# Ampli_audio.net
KiCad netlist of a schematic drawn in EasyEDA
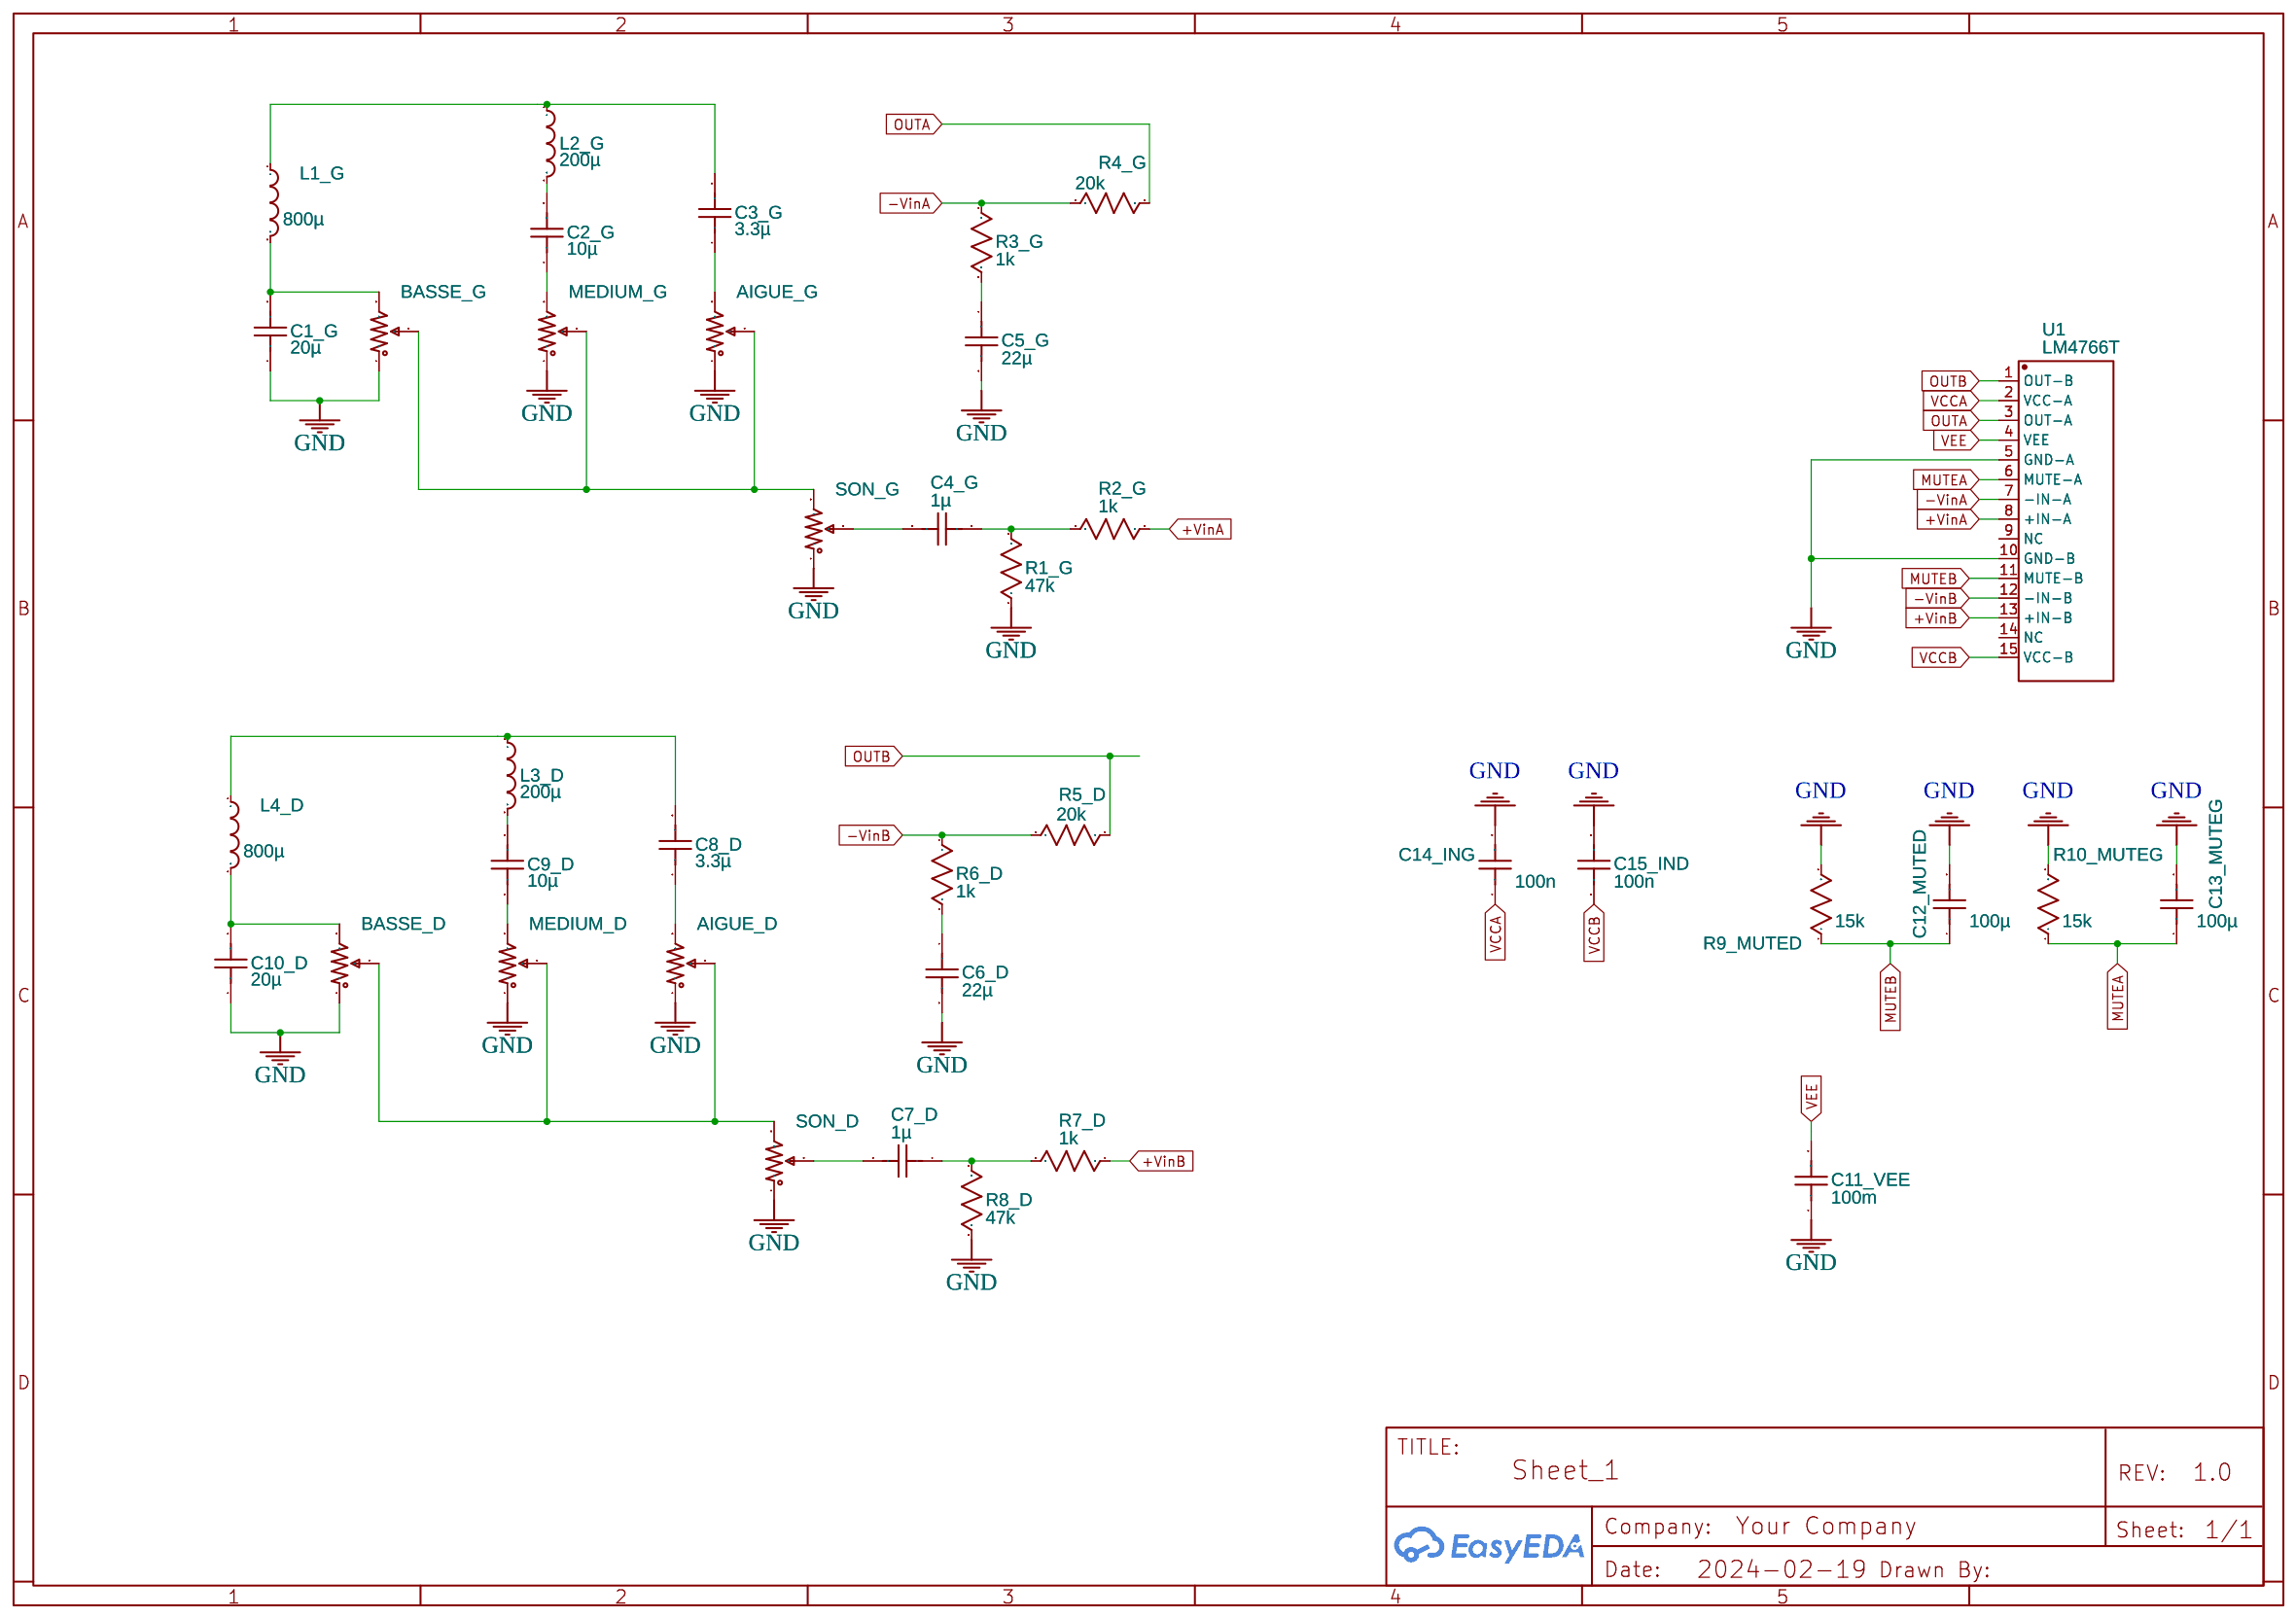
[diagram p0: schematic sheet]

(export (version "E")
  (design (tool "Eeschema 10.0.6"))
  (components
    (comp (ref "AIGUE_D") (value "R_3386P_US") (libsource (lib "") (part "R_3386P_US_3")))
    (comp (ref "AIGUE_G") (value "R_3386P_US") (libsource (lib "") (part "R_3386P_US_4")))
    (comp (ref "BASSE_D") (value "R_3386P_US") (libsource (lib "") (part "R_3386P_US_6")))
    (comp (ref "BASSE_G") (value "R_3386P_US") (libsource (lib "") (part "R_3386P_US_7")))
    (comp (ref "C1_G") (value "20µ") (libsource (lib "") (part "C_0603_US_11")))
    (comp (ref "C2_G") (value "10µ") (libsource (lib "") (part "C_0603_US_14")))
    (comp (ref "C3_G") (value "3.3µ") (libsource (lib "") (part "C_0603_US_12")))
    (comp (ref "C4_G") (value "1µ") (libsource (lib "") (part "C_0603_US_3")))
    (comp (ref "C5_G") (value "22µ") (libsource (lib "") (part "C_0603_US_10")))
    (comp (ref "C6_D") (value "22µ") (libsource (lib "") (part "C_0603_US_13")))
    (comp (ref "C7_D") (value "1µ") (libsource (lib "") (part "C_0603_US_6")))
    (comp (ref "C8_D") (value "3.3µ") (libsource (lib "") (part "C_0603_US_8")))
    (comp (ref "C9_D") (value "10µ") (libsource (lib "") (part "C_0603_US")))
    (comp (ref "C10_D") (value "20µ") (libsource (lib "") (part "C_0603_US_5")))
    (comp (ref "C11_VEE") (value "100m") (libsource (lib "") (part "C_0603_US_7")))
    (comp (ref "C12_MUTED") (value "100µ") (libsource (lib "") (part "C_0603_US_9")))
    (comp (ref "C13_MUTEG") (value "100µ") (libsource (lib "") (part "C_0603_US_4")))
    (comp (ref "C14_ING") (value "100n") (libsource (lib "") (part "C_0603_US_1")))
    (comp (ref "C15_IND") (value "100n") (libsource (lib "") (part "C_0603_US_2")))
    (comp (ref "L1_G") (value "800µ") (libsource (lib "") (part "L0603_US_3")))
    (comp (ref "L2_G") (value "200µ") (libsource (lib "") (part "L0603_US_1")))
    (comp (ref "L3_D") (value "200µ") (libsource (lib "") (part "L0603_US")))
    (comp (ref "L4_D") (value "800µ") (libsource (lib "") (part "L0603_US_2")))
    (comp (ref "MEDIUM_D") (value "R_3386P_US") (libsource (lib "") (part "R_3386P_US")))
    (comp (ref "MEDIUM_G") (value "R_3386P_US") (libsource (lib "") (part "R_3386P_US_1")))
    (comp (ref "R1_G") (value "47k") (libsource (lib "") (part "R_0603_US_5")))
    (comp (ref "R2_G") (value "1k") (libsource (lib "") (part "R_0603_US_3")))
    (comp (ref "R3_G") (value "1k") (libsource (lib "") (part "R_0603_US")))
    (comp (ref "R4_G") (value "20k") (libsource (lib "") (part "R_0603_US_6")))
    (comp (ref "R5_D") (value "20k") (libsource (lib "") (part "R_0603_US_1")))
    (comp (ref "R6_D") (value "1k") (libsource (lib "") (part "R_0603_US_7")))
    (comp (ref "R7_D") (value "1k") (libsource (lib "") (part "R_0603_US_4")))
    (comp (ref "R8_D") (value "47k") (libsource (lib "") (part "R_0603_US_2")))
    (comp (ref "R9_MUTED") (value "15k") (libsource (lib "") (part "R_0603_US_8")))
    (comp (ref "R10_MUTEG") (value "15k") (libsource (lib "") (part "R_0603_US_9")))
    (comp (ref "SON_D") (value "R_3386P_US") (libsource (lib "") (part "R_3386P_US_5")))
    (comp (ref "SON_G") (value "R_3386P_US") (libsource (lib "") (part "R_3386P_US_2")))
    (comp (ref "U1")
      (value "LM4766T")
      (fields (field (name "Manufacturer Part") "LM4766T/NOPB") (field (name "Manufacturer") "TI(德州仪器)"))
      (libsource (lib "") (part "LM4766T"))
    )
  )
  (nets
    (net (code "1") (name "+VinA") (class "Default")
      (node (ref "R2_G") (pin "1") (pinfunction "1_1") (pintype "unspecified"))
      (node (ref "U1") (pin "8") (pinfunction "+IN-A_8") (pintype "unspecified"))
    )
    (net (code "2") (name "+VinB") (class "Default")
      (node (ref "R7_D") (pin "1") (pinfunction "1_1") (pintype "unspecified"))
      (node (ref "U1") (pin "13") (pinfunction "+IN-B_13") (pintype "unspecified"))
    )
    (net (code "3") (name "-VinA") (class "Default")
      (node (ref "R3_G") (pin "1") (pinfunction "1_1") (pintype "unspecified"))
      (node (ref "R4_G") (pin "1") (pinfunction "1_1") (pintype "unspecified"))
      (node (ref "U1") (pin "7") (pinfunction "-IN-A_7") (pintype "unspecified"))
    )
    (net (code "4") (name "-VinB") (class "Default")
      (node (ref "R5_D") (pin "1") (pinfunction "1_1") (pintype "unspecified"))
      (node (ref "R6_D") (pin "1") (pinfunction "1_1") (pintype "unspecified"))
      (node (ref "U1") (pin "12") (pinfunction "-IN-B_12") (pintype "unspecified"))
    )
    (net (code "5") (name "GND") (class "Default")
      (node (ref "AIGUE_D") (pin "1") (pinfunction "1_1") (pintype "unspecified"))
      (node (ref "AIGUE_G") (pin "1") (pinfunction "1_1") (pintype "unspecified"))
      (node (ref "BASSE_D") (pin "1") (pinfunction "1_1") (pintype "unspecified"))
      (node (ref "BASSE_G") (pin "1") (pinfunction "1_1") (pintype "unspecified"))
      (node (ref "C10_D") (pin "1") (pinfunction "1_1") (pintype "unspecified"))
      (node (ref "C11_VEE") (pin "1") (pinfunction "1_1") (pintype "unspecified"))
      (node (ref "C12_MUTED") (pin "2") (pinfunction "2_2") (pintype "unspecified"))
      (node (ref "C13_MUTEG") (pin "2") (pinfunction "2_2") (pintype "unspecified"))
      (node (ref "C14_ING") (pin "2") (pinfunction "2_2") (pintype "unspecified"))
      (node (ref "C15_IND") (pin "2") (pinfunction "2_2") (pintype "unspecified"))
      (node (ref "C1_G") (pin "1") (pinfunction "1_1") (pintype "unspecified"))
      (node (ref "C5_G") (pin "2") (pinfunction "2_2") (pintype "unspecified"))
      (node (ref "C6_D") (pin "2") (pinfunction "2_2") (pintype "unspecified"))
      (node (ref "MEDIUM_D") (pin "1") (pinfunction "1_1") (pintype "unspecified"))
      (node (ref "MEDIUM_G") (pin "1") (pinfunction "1_1") (pintype "unspecified"))
      (node (ref "R10_MUTEG") (pin "2") (pinfunction "2_2") (pintype "unspecified"))
      (node (ref "R1_G") (pin "1") (pinfunction "1_1") (pintype "unspecified"))
      (node (ref "R8_D") (pin "1") (pinfunction "1_1") (pintype "unspecified"))
      (node (ref "R9_MUTED") (pin "2") (pinfunction "2_2") (pintype "unspecified"))
      (node (ref "SON_D") (pin "1") (pinfunction "1_1") (pintype "unspecified"))
      (node (ref "SON_G") (pin "1") (pinfunction "1_1") (pintype "unspecified"))
      (node (ref "U1") (pin "10") (pinfunction "GND-B_10") (pintype "unspecified"))
      (node (ref "U1") (pin "5") (pinfunction "GND-A_5") (pintype "unspecified"))
    )
    (net (code "6") (name "MUTEA") (class "Default")
      (node (ref "C13_MUTEG") (pin "1") (pinfunction "1_1") (pintype "unspecified"))
      (node (ref "R10_MUTEG") (pin "1") (pinfunction "1_1") (pintype "unspecified"))
      (node (ref "U1") (pin "6") (pinfunction "MUTE-A_6") (pintype "unspecified"))
    )
    (net (code "7") (name "MUTEB") (class "Default")
      (node (ref "C12_MUTED") (pin "1") (pinfunction "1_1") (pintype "unspecified"))
      (node (ref "R9_MUTED") (pin "1") (pinfunction "1_1") (pintype "unspecified"))
      (node (ref "U1") (pin "11") (pinfunction "MUTE-B_11") (pintype "unspecified"))
    )
    (net (code "8") (name "Net-(AIGUE_D-Pad2)") (class "Default")
      (node (ref "AIGUE_D") (pin "2") (pinfunction "2_2") (pintype "unspecified"))
      (node (ref "BASSE_D") (pin "2") (pinfunction "2_2") (pintype "unspecified"))
      (node (ref "MEDIUM_D") (pin "2") (pinfunction "2_2") (pintype "unspecified"))
      (node (ref "SON_D") (pin "3") (pinfunction "3_3") (pintype "unspecified"))
    )
    (net (code "9") (name "Net-(AIGUE_D-Pad3)") (class "Default")
      (node (ref "AIGUE_D") (pin "3") (pinfunction "3_3") (pintype "unspecified"))
      (node (ref "C8_D") (pin "1") (pinfunction "1_1") (pintype "unspecified"))
    )
    (net (code "10") (name "Net-(AIGUE_G-Pad2)") (class "Default")
      (node (ref "AIGUE_G") (pin "2") (pinfunction "2_2") (pintype "unspecified"))
      (node (ref "BASSE_G") (pin "2") (pinfunction "2_2") (pintype "unspecified"))
      (node (ref "MEDIUM_G") (pin "2") (pinfunction "2_2") (pintype "unspecified"))
      (node (ref "SON_G") (pin "3") (pinfunction "3_3") (pintype "unspecified"))
    )
    (net (code "11") (name "Net-(AIGUE_G-Pad3)") (class "Default")
      (node (ref "AIGUE_G") (pin "3") (pinfunction "3_3") (pintype "unspecified"))
      (node (ref "C3_G") (pin "1") (pinfunction "1_1") (pintype "unspecified"))
    )
    (net (code "12") (name "Net-(BASSE_D-Pad3)") (class "Default")
      (node (ref "BASSE_D") (pin "3") (pinfunction "3_3") (pintype "unspecified"))
      (node (ref "C10_D") (pin "2") (pinfunction "2_2") (pintype "unspecified"))
      (node (ref "L4_D") (pin "2") (pinfunction "2_2") (pintype "unspecified"))
    )
    (net (code "13") (name "Net-(BASSE_G-Pad3)") (class "Default")
      (node (ref "BASSE_G") (pin "3") (pinfunction "3_3") (pintype "unspecified"))
      (node (ref "C1_G") (pin "2") (pinfunction "2_2") (pintype "unspecified"))
      (node (ref "L1_G") (pin "2") (pinfunction "2_2") (pintype "unspecified"))
    )
    (net (code "14") (name "Net-(C2_G-Pad1)") (class "Default")
      (node (ref "C2_G") (pin "1") (pinfunction "1_1") (pintype "unspecified"))
      (node (ref "MEDIUM_G") (pin "3") (pinfunction "3_3") (pintype "unspecified"))
    )
    (net (code "15") (name "Net-(C2_G-Pad2)") (class "Default")
      (node (ref "C2_G") (pin "2") (pinfunction "2_2") (pintype "unspecified"))
      (node (ref "L2_G") (pin "2") (pinfunction "2_2") (pintype "unspecified"))
    )
    (net (code "16") (name "Net-(C3_G-Pad2)") (class "Default")
      (node (ref "C3_G") (pin "2") (pinfunction "2_2") (pintype "unspecified"))
      (node (ref "L1_G") (pin "1") (pinfunction "1_1") (pintype "unspecified"))
      (node (ref "L2_G") (pin "1") (pinfunction "1_1") (pintype "unspecified"))
    )
    (net (code "17") (name "Net-(C4_G-Pad1)") (class "Default")
      (node (ref "C4_G") (pin "1") (pinfunction "1_1") (pintype "unspecified"))
      (node (ref "R1_G") (pin "2") (pinfunction "2_2") (pintype "unspecified"))
      (node (ref "R2_G") (pin "2") (pinfunction "2_2") (pintype "unspecified"))
    )
    (net (code "18") (name "Net-(C4_G-Pad2)") (class "Default")
      (node (ref "C4_G") (pin "2") (pinfunction "2_2") (pintype "unspecified"))
      (node (ref "SON_G") (pin "2") (pinfunction "2_2") (pintype "unspecified"))
    )
    (net (code "19") (name "Net-(C5_G-Pad1)") (class "Default")
      (node (ref "C5_G") (pin "1") (pinfunction "1_1") (pintype "unspecified"))
      (node (ref "R3_G") (pin "2") (pinfunction "2_2") (pintype "unspecified"))
    )
    (net (code "20") (name "Net-(C6_D-Pad1)") (class "Default")
      (node (ref "C6_D") (pin "1") (pinfunction "1_1") (pintype "unspecified"))
      (node (ref "R6_D") (pin "2") (pinfunction "2_2") (pintype "unspecified"))
    )
    (net (code "21") (name "Net-(C7_D-Pad1)") (class "Default")
      (node (ref "C7_D") (pin "1") (pinfunction "1_1") (pintype "unspecified"))
      (node (ref "R7_D") (pin "2") (pinfunction "2_2") (pintype "unspecified"))
      (node (ref "R8_D") (pin "2") (pinfunction "2_2") (pintype "unspecified"))
    )
    (net (code "22") (name "Net-(C7_D-Pad2)") (class "Default")
      (node (ref "C7_D") (pin "2") (pinfunction "2_2") (pintype "unspecified"))
      (node (ref "SON_D") (pin "2") (pinfunction "2_2") (pintype "unspecified"))
    )
    (net (code "23") (name "Net-(C8_D-Pad2)") (class "Default")
      (node (ref "C8_D") (pin "2") (pinfunction "2_2") (pintype "unspecified"))
      (node (ref "L3_D") (pin "1") (pinfunction "1_1") (pintype "unspecified"))
      (node (ref "L4_D") (pin "1") (pinfunction "1_1") (pintype "unspecified"))
    )
    (net (code "24") (name "Net-(C9_D-Pad1)") (class "Default")
      (node (ref "C9_D") (pin "1") (pinfunction "1_1") (pintype "unspecified"))
      (node (ref "MEDIUM_D") (pin "3") (pinfunction "3_3") (pintype "unspecified"))
    )
    (net (code "25") (name "Net-(C9_D-Pad2)") (class "Default")
      (node (ref "C9_D") (pin "2") (pinfunction "2_2") (pintype "unspecified"))
      (node (ref "L3_D") (pin "2") (pinfunction "2_2") (pintype "unspecified"))
    )
    (net (code "26") (name "OUTA") (class "Default")
      (node (ref "R4_G") (pin "2") (pinfunction "2_2") (pintype "unspecified"))
      (node (ref "U1") (pin "3") (pinfunction "OUT-A_3") (pintype "unspecified"))
    )
    (net (code "27") (name "OUTB") (class "Default")
      (node (ref "R5_D") (pin "2") (pinfunction "2_2") (pintype "unspecified"))
      (node (ref "U1") (pin "1") (pinfunction "OUT-B_1") (pintype "unspecified"))
    )
    (net (code "28") (name "VCCA") (class "Default")
      (node (ref "C14_ING") (pin "1") (pinfunction "1_1") (pintype "unspecified"))
      (node (ref "U1") (pin "2") (pinfunction "VCC-A_2") (pintype "unspecified"))
    )
    (net (code "29") (name "VCCB") (class "Default")
      (node (ref "C15_IND") (pin "1") (pinfunction "1_1") (pintype "unspecified"))
      (node (ref "U1") (pin "15") (pinfunction "VCC-B_15") (pintype "unspecified"))
    )
    (net (code "30") (name "VEE") (class "Default")
      (node (ref "C11_VEE") (pin "2") (pinfunction "2_2") (pintype "unspecified"))
      (node (ref "U1") (pin "4") (pinfunction "VEE_4") (pintype "unspecified"))
    )
    (net (code "31") (name "unconnected-(U1-NC-Pad9)") (class "Default")
      (node (ref "U1") (pin "9") (pinfunction "NC_9") (pintype "unspecified"))
    )
    (net (code "32") (name "unconnected-(U1-NC-Pad14)") (class "Default")
      (node (ref "U1") (pin "14") (pinfunction "NC_14") (pintype "unspecified"))
    )
  )
)
